# logic_000.net
KiCad netlist of a schematic drawn in Altium Designer
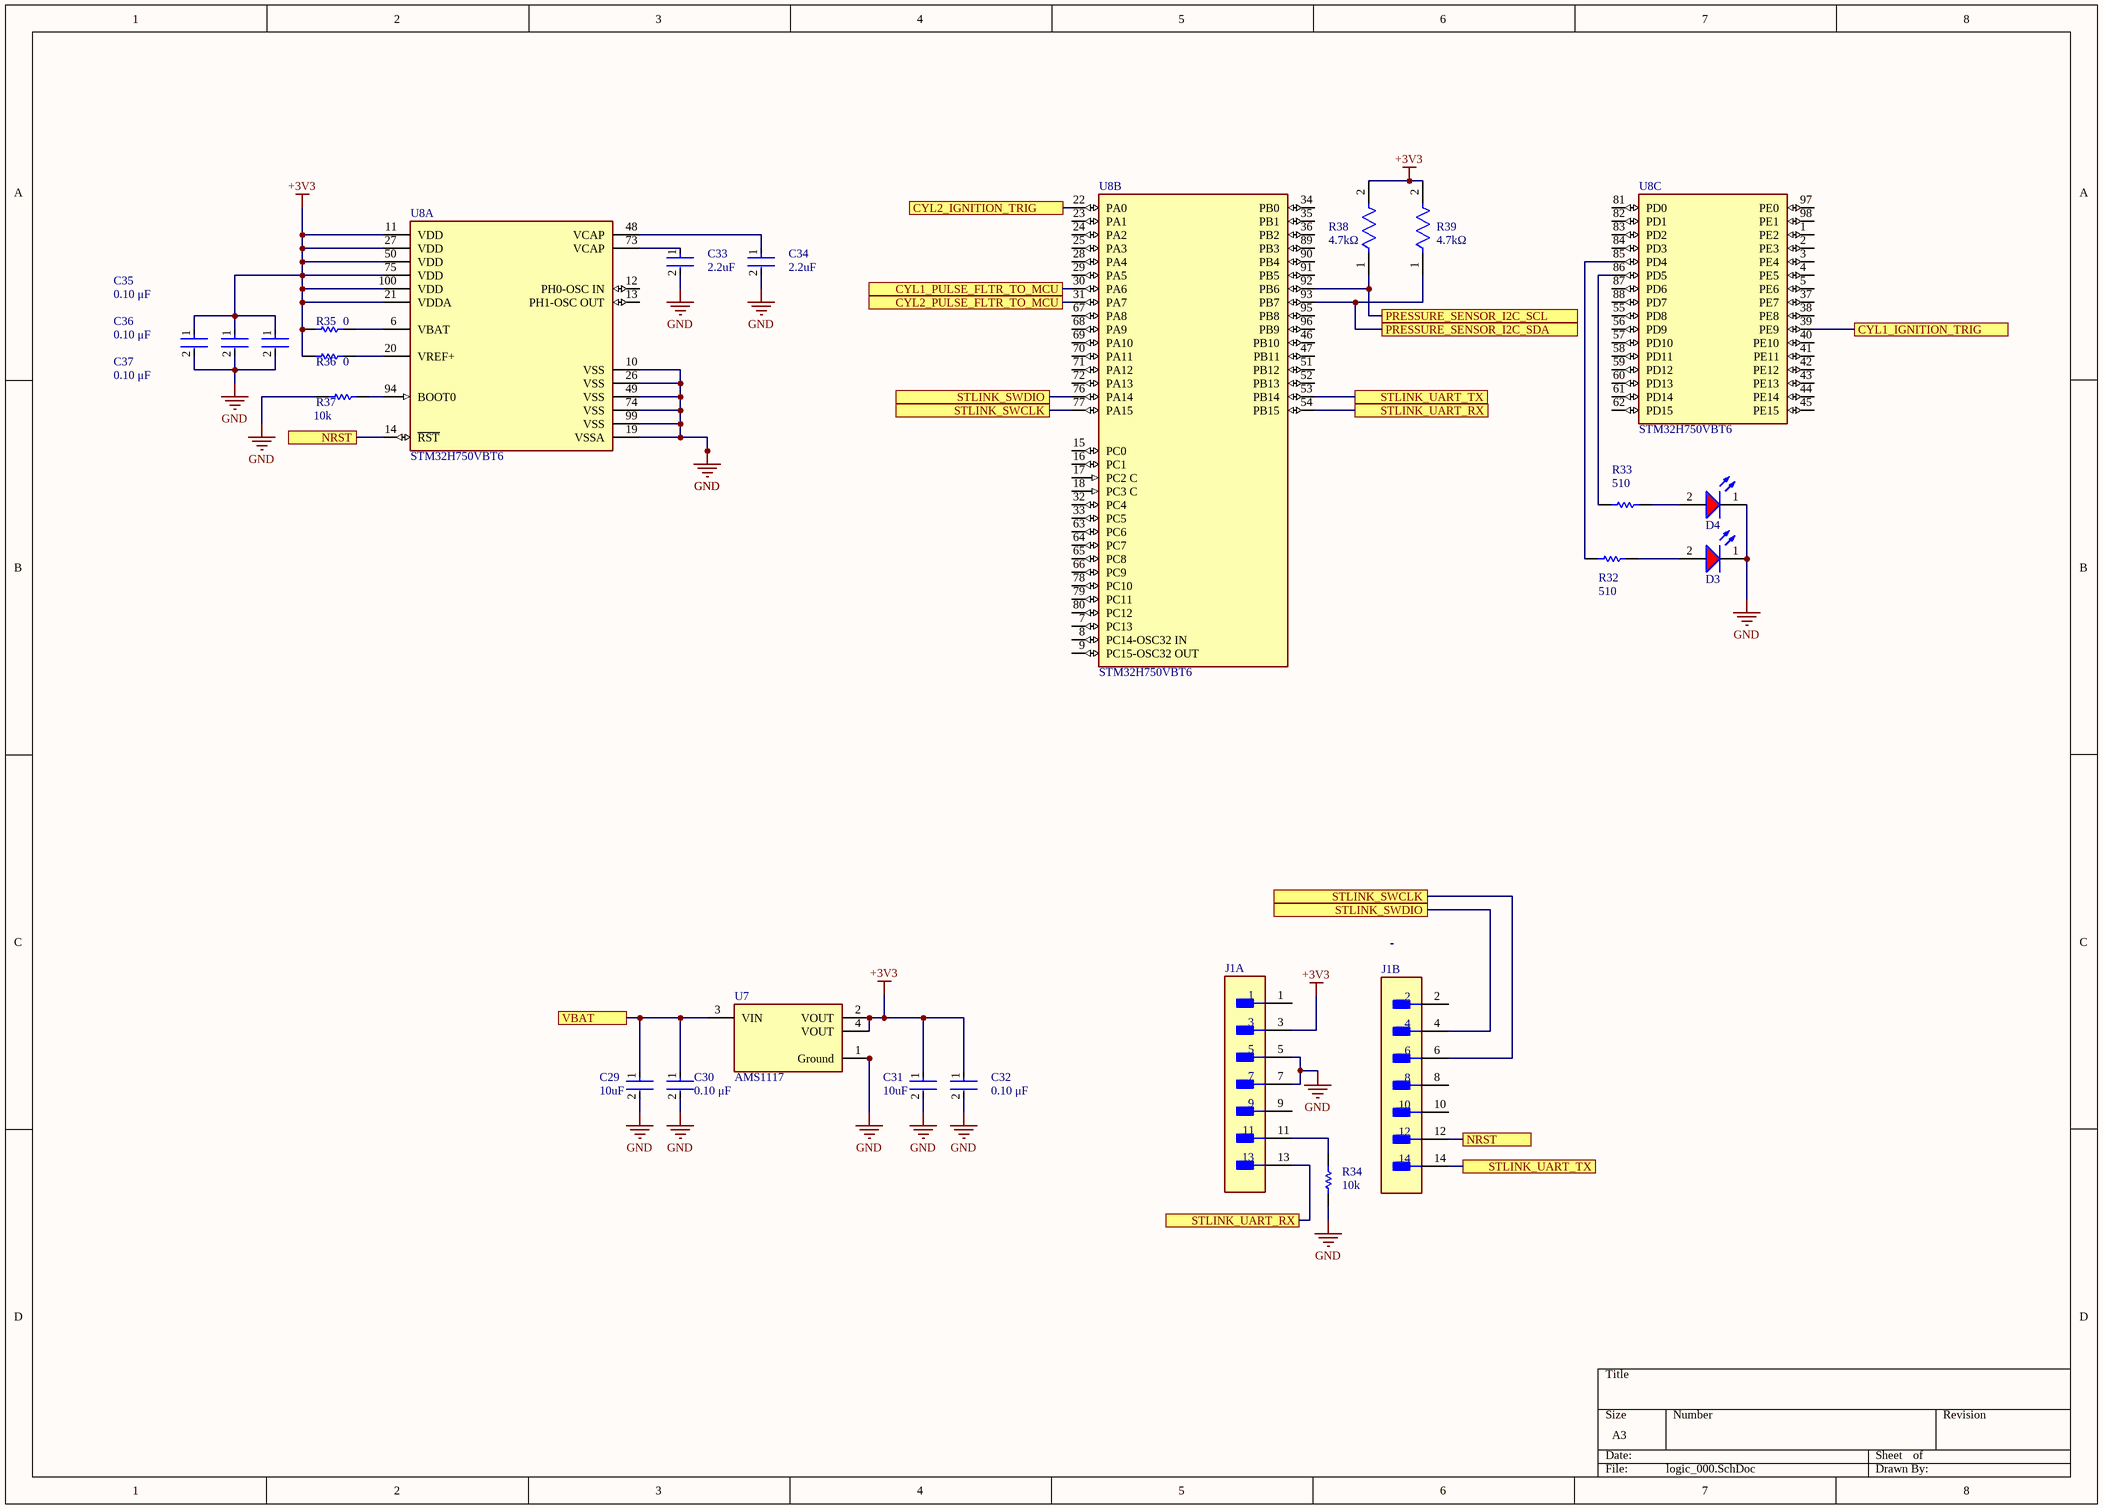
[diagram p0: logic_000.SchDoc]

(export (version "E")
  (design (tool "Eeschema 10.0.6"))
  (components
    (comp (ref "C29")
      (value "CL05A106MP5NUNC")
      (footprint "FP-CL05A106MP5NUNC-MFG")
      (description "CAP CER 10UF 10V X5R 0402")
      (fields
        (field (name "OCTOPART") "https://octopart.com/cl05a106mp5nunc-samsung-22457395")
        (field (name "TOLERANCE") "20%")
        (field (name "CAPACITANCE") "10uF")
      )
      (libsource (lib "Altium Content Vault") (part "b4654b650e69147ec39a6b967a45e02"))
    )
    (comp (ref "C30")
      (value "C0402C104K8PACTU")
      (footprint "FP-C0402-BB-MFG")
      (description "CAP CER 0.1UF 10V X5R 0402")
      (fields
        (field (name "CAPACITANCE") "0.10 μF")
        (field (name "MANUFACTURER") "Kemet")
        (field (name "TOLERANCE") "0.1")
      )
      (libsource (lib "Altium Content Vault") (part "b4654b650e69147ec39a6b967a45e02"))
    )
    (comp (ref "C31")
      (value "CL05A106MP5NUNC")
      (footprint "FP-CL05A106MP5NUNC-MFG")
      (description "CAP CER 10UF 10V X5R 0402")
      (fields
        (field (name "OCTOPART") "https://octopart.com/cl05a106mp5nunc-samsung-22457395")
        (field (name "TOLERANCE") "20%")
        (field (name "CAPACITANCE") "10uF")
      )
      (libsource (lib "Altium Content Vault") (part "b4654b650e69147ec39a6b967a45e02"))
    )
    (comp (ref "C32")
      (value "C0402C104K8PACTU")
      (footprint "FP-C0402-BB-MFG")
      (description "CAP CER 0.1UF 10V X5R 0402")
      (fields
        (field (name "CAPACITANCE") "0.10 μF")
        (field (name "MANUFACTURER") "Kemet")
        (field (name "TOLERANCE") "0.1")
      )
      (libsource (lib "Altium Content Vault") (part "b4654b650e69147ec39a6b967a45e02"))
    )
    (comp (ref "C33")
      (value "GRM155R61A225KE95D")
      (footprint "FP-GRM155-0_05-MFG")
      (description "CAP CER 2.2UF 10V X5R 0402")
      (fields (field (name "CAPACITANCE") "2.2uF") (field (name "TOLERANCE") "10%"))
      (libsource (lib "Altium Content Vault") (part "b4654b650e69147ec39a6b967a45e02"))
    )
    (comp (ref "C34")
      (value "GRM155R61A225KE95D")
      (footprint "FP-GRM155-0_05-MFG")
      (description "CAP CER 2.2UF 10V X5R 0402")
      (fields (field (name "CAPACITANCE") "2.2uF") (field (name "TOLERANCE") "10%"))
      (libsource (lib "Altium Content Vault") (part "b4654b650e69147ec39a6b967a45e02"))
    )
    (comp (ref "C35")
      (value "0.10 μF")
      (footprint "FP-C0402-BB-MFG")
      (description "CAP CER 0.1UF 10V X5R 0402")
      (fields (field (name "MANUFACTURER") "Kemet") (field (name "TOLERANCE") "0.1"))
      (libsource (lib "Altium Content Vault") (part "b4654b650e69147ec39a6b967a45e02"))
    )
    (comp (ref "C36")
      (value "0.10 μF")
      (footprint "FP-C0402-BB-MFG")
      (description "CAP CER 0.1UF 10V X5R 0402")
      (fields (field (name "MANUFACTURER") "Kemet") (field (name "TOLERANCE") "0.1"))
      (libsource (lib "Altium Content Vault") (part "b4654b650e69147ec39a6b967a45e02"))
    )
    (comp (ref "C37")
      (value "0.10 μF")
      (footprint "FP-C0402-BB-MFG")
      (description "CAP CER 0.1UF 10V X5R 0402")
      (fields (field (name "MANUFACTURER") "Kemet") (field (name "TOLERANCE") "0.1"))
      (libsource (lib "Altium Content Vault") (part "b4654b650e69147ec39a6b967a45e02"))
    )
    (comp (ref "D3")
      (value "150080SS75000")
      (footprint "WL-SMCW_0805_150080xx75000")
      (description "Led, Red, 630 Nm, 1.9 V, 30 Ma, 60 Mcd Rohs Compliant: Yes")
      (libsource (lib "Altium Content Vault") (part "LED_Red_2A-1K"))
    )
    (comp (ref "D4")
      (value "150080SS75000")
      (footprint "WL-SMCW_0805_150080xx75000")
      (description "Led, Red, 630 Nm, 1.9 V, 30 Ma, 60 Mcd Rohs Compliant: Yes")
      (libsource (lib "Altium Content Vault") (part "LED_Red_2A-1K"))
    )
    (comp (ref "J1")
      (value "FTSH-107-01-L-DV-K")
      (footprint "FP-FTSH-107-01-L-DV-K-MFG")
      (description "CONN HEADER SMD 14POS 1.27MM")
      (libsource (lib "Altium Content Vault") (part "7644e1a88aa4da17242a9b8d8257442"))
    )
    (comp (ref "R32")
      (value "510")
      (footprint "RESC1005X40X25LL05T10")
      (fields (field (name "MANUFACTURER") "Yageo / Phycomp") (field (name "PART NUMBER") "RC0402FR-07510RL"))
      (libsource (lib "Altium Content Vault") (part "RES"))
    )
    (comp (ref "R33")
      (value "510")
      (footprint "RESC1005X40X25LL05T10")
      (fields (field (name "MANUFACTURER") "Yageo / Phycomp") (field (name "PART NUMBER") "RC0402FR-07510RL"))
      (libsource (lib "Altium Content Vault") (part "RES"))
    )
    (comp (ref "R34")
      (value "10k")
      (footprint "RESC1005X40X25LL05T10")
      (fields (field (name "PART NUMBER") "RC0402FR-0710KL") (field (name "MANUFACTURER") "Yageo / Phycomp"))
      (libsource (lib "Altium Content Vault") (part "RES"))
    )
    (comp (ref "R35")
      (value "0")
      (footprint "RESC1005X40X25NL05T10")
      (fields (field (name "MANUFACTURER") "Yageo / Phycomp") (field (name "PART NUMBER") "RC0402JR-070RL"))
      (libsource (lib "Altium Content Vault") (part "RES"))
    )
    (comp (ref "R36")
      (value "0")
      (footprint "RESC1005X40X25NL05T10")
      (fields (field (name "MANUFACTURER") "Yageo / Phycomp") (field (name "PART NUMBER") "RC0402JR-070RL"))
      (libsource (lib "Altium Content Vault") (part "RES"))
    )
    (comp (ref "R37")
      (value "10k")
      (footprint "RESC1005X40X25LL05T10")
      (fields (field (name "PART NUMBER") "RC0402FR-0710KL") (field (name "MANUFACTURER") "Yageo / Phycomp"))
      (libsource (lib "Altium Content Vault") (part "RES"))
    )
    (comp (ref "R38")
      (value "RC0402JR-074K7L")
      (footprint "FP-RC0402-0_4-MFG")
      (fields (field (name "TOLERANCE") "5%") (field (name "RESISTANCE") "4.7kΩ"))
      (libsource (lib "Altium Content Vault") (part "RC0402JR-074K7L"))
    )
    (comp (ref "R39")
      (value "RC0402JR-074K7L")
      (footprint "FP-RC0402-0_4-MFG")
      (fields (field (name "TOLERANCE") "5%") (field (name "RESISTANCE") "4.7kΩ"))
      (libsource (lib "Altium Content Vault") (part "RC0402JR-074K7L"))
    )
    (comp (ref "U7")
      (value "AMS1117-3.3")
      (footprint "FP-AMS1117-IPC_C")
      (description "LDO Voltage Regulators 1A, 3.3V")
      (fields
        (field (name "PACKAGE") "AMS1117")
        (field (name "OCTOPART") "https://octopart.com/ams1117-3.3-advanced+monolithic+systems-25899300")
        (field (name "MANUFACTURER") "Advanced Monolithic Systems")
      )
      (libsource (lib "Altium Content Vault") (part "8bdbb5f8e77002000e30dd2845d0354"))
    )
    (comp (ref "U8")
      (value "STM32H750VBT6")
      (footprint "FP-LQFP100-1L-MFG")
      (description "IC MCU 32BIT 128KB FLASH 100LQFP")
      (fields
        (field (name "OCTOPART") "https://octopart.com/stm32h750vbt6-stmicroelectronics-94048547")
        (field (name "MANUFACTURER") "STMicroelectronics")
      )
      (libsource (lib "Altium Content Vault") (part "aca449acb2b80670ba40d015d68dc7a"))
    )
  )
  (nets
    (net (code "1") (name "+3V3") (class "Default")
      (node (ref "C31") (pin "1") (pinfunction "1_1") (pintype "passive"))
      (node (ref "C32") (pin "1") (pinfunction "1_1") (pintype "passive"))
      (node (ref "C35") (pin "1") (pinfunction "1_1") (pintype "passive"))
      (node (ref "C36") (pin "1") (pinfunction "1_1") (pintype "passive"))
      (node (ref "C37") (pin "1") (pinfunction "1_1") (pintype "passive"))
      (node (ref "J1") (pin "3") (pinfunction "3_3") (pintype "passive"))
      (node (ref "R35") (pin "1") (pinfunction "1_1") (pintype "passive"))
      (node (ref "R36") (pin "1") (pinfunction "1_1") (pintype "passive"))
      (node (ref "R38") (pin "2") (pinfunction "2_2") (pintype "passive"))
      (node (ref "R39") (pin "2") (pinfunction "2_2") (pintype "passive"))
      (node (ref "U7") (pin "2") (pinfunction "VOUT_2") (pintype "passive"))
      (node (ref "U7") (pin "4") (pinfunction "VOUT_4") (pintype "passive"))
      (node (ref "U8") (pin "100") (pinfunction "VDD_100") (pintype "power_in"))
      (node (ref "U8") (pin "11") (pinfunction "VDD_11") (pintype "power_in"))
      (node (ref "U8") (pin "21") (pinfunction "VDDA_21") (pintype "power_in"))
      (node (ref "U8") (pin "27") (pinfunction "VDD_27") (pintype "power_in"))
      (node (ref "U8") (pin "50") (pinfunction "VDD_50") (pintype "power_in"))
      (node (ref "U8") (pin "75") (pinfunction "VDD_75") (pintype "power_in"))
    )
    (net (code "2") (name "/CYL1_IGNITION_TRIG") (class "Default")
      (node (ref "U8") (pin "39") (pinfunction "PE9_39") (pintype "bidirectional"))
    )
    (net (code "3") (name "/CYL1_PULSE_FLTR_TO_MCU") (class "Default")
      (node (ref "U8") (pin "30") (pinfunction "PA6_30") (pintype "bidirectional"))
    )
    (net (code "4") (name "/CYL2_IGNITION_TRIG") (class "Default")
      (node (ref "U8") (pin "22") (pinfunction "PA0_22") (pintype "bidirectional"))
    )
    (net (code "5") (name "/CYL2_PULSE_FLTR_TO_MCU") (class "Default")
      (node (ref "U8") (pin "31") (pinfunction "PA7_31") (pintype "bidirectional"))
    )
    (net (code "6") (name "/NRST") (class "Default")
      (node (ref "J1") (pin "12") (pinfunction "12_12") (pintype "passive"))
      (node (ref "U8") (pin "14") (pinfunction "~{RST}_14") (pintype "bidirectional"))
    )
    (net (code "7") (name "/PRESSURE_SENSOR_I2C_SCL") (class "Default")
      (node (ref "R38") (pin "1") (pinfunction "1_1") (pintype "passive"))
      (node (ref "U8") (pin "92") (pinfunction "PB6_92") (pintype "bidirectional"))
    )
    (net (code "8") (name "/PRESSURE_SENSOR_I2C_SDA") (class "Default")
      (node (ref "R39") (pin "1") (pinfunction "1_1") (pintype "passive"))
      (node (ref "U8") (pin "93") (pinfunction "PB7_93") (pintype "bidirectional"))
    )
    (net (code "9") (name "/STLINK_SWCLK") (class "Default")
      (node (ref "J1") (pin "6") (pinfunction "6_6") (pintype "passive"))
      (node (ref "U8") (pin "77") (pinfunction "PA15_77") (pintype "bidirectional"))
    )
    (net (code "10") (name "/STLINK_SWDIO") (class "Default")
      (node (ref "J1") (pin "4") (pinfunction "4_4") (pintype "passive"))
      (node (ref "U8") (pin "76") (pinfunction "PA14_76") (pintype "bidirectional"))
    )
    (net (code "11") (name "/STLINK_UART_RX") (class "Default")
      (node (ref "J1") (pin "13") (pinfunction "13_13") (pintype "passive"))
      (node (ref "U8") (pin "54") (pinfunction "PB15_54") (pintype "bidirectional"))
    )
    (net (code "12") (name "/STLINK_UART_TX") (class "Default")
      (node (ref "J1") (pin "14") (pinfunction "14_14") (pintype "passive"))
      (node (ref "U8") (pin "53") (pinfunction "PB14_53") (pintype "bidirectional"))
    )
    (net (code "13") (name "/VBAT") (class "Default")
      (node (ref "C29") (pin "1") (pinfunction "1_1") (pintype "passive"))
      (node (ref "C30") (pin "1") (pinfunction "1_1") (pintype "passive"))
      (node (ref "U7") (pin "3") (pinfunction "VIN_3") (pintype "power_in"))
    )
    (net (code "14") (name "GND") (class "Default")
      (node (ref "C29") (pin "2") (pinfunction "2_2") (pintype "passive"))
      (node (ref "C30") (pin "2") (pinfunction "2_2") (pintype "passive"))
      (node (ref "C31") (pin "2") (pinfunction "2_2") (pintype "passive"))
      (node (ref "C32") (pin "2") (pinfunction "2_2") (pintype "passive"))
      (node (ref "C33") (pin "2") (pinfunction "2_2") (pintype "passive"))
      (node (ref "C34") (pin "2") (pinfunction "2_2") (pintype "passive"))
      (node (ref "C35") (pin "2") (pinfunction "2_2") (pintype "passive"))
      (node (ref "C36") (pin "2") (pinfunction "2_2") (pintype "passive"))
      (node (ref "C37") (pin "2") (pinfunction "2_2") (pintype "passive"))
      (node (ref "D3") (pin "1") (pinfunction "K_1") (pintype "passive"))
      (node (ref "D4") (pin "1") (pinfunction "K_1") (pintype "passive"))
      (node (ref "J1") (pin "5") (pinfunction "5_5") (pintype "passive"))
      (node (ref "J1") (pin "7") (pinfunction "7_7") (pintype "passive"))
      (node (ref "R34") (pin "1") (pinfunction "1_1") (pintype "passive"))
      (node (ref "R37") (pin "1") (pinfunction "1_1") (pintype "passive"))
      (node (ref "U7") (pin "1") (pinfunction "Ground_1") (pintype "power_in"))
      (node (ref "U8") (pin "10") (pinfunction "VSS_10") (pintype "power_in"))
      (node (ref "U8") (pin "19") (pinfunction "VSSA_19") (pintype "power_in"))
      (node (ref "U8") (pin "26") (pinfunction "VSS_26") (pintype "power_in"))
      (node (ref "U8") (pin "49") (pinfunction "VSS_49") (pintype "power_in"))
      (node (ref "U8") (pin "74") (pinfunction "VSS_74") (pintype "power_in"))
      (node (ref "U8") (pin "99") (pinfunction "VSS_99") (pintype "power_in"))
    )
    (net (code "15") (name "Net-(C33-Pad1)") (class "Default")
      (node (ref "C33") (pin "1") (pinfunction "1_1") (pintype "passive"))
      (node (ref "U8") (pin "73") (pinfunction "VCAP_73") (pintype "power_in"))
    )
    (net (code "16") (name "Net-(C34-Pad1)") (class "Default")
      (node (ref "C34") (pin "1") (pinfunction "1_1") (pintype "passive"))
      (node (ref "U8") (pin "48") (pinfunction "VCAP_48") (pintype "power_in"))
    )
    (net (code "17") (name "Net-(D3-A)") (class "Default")
      (node (ref "D3") (pin "2") (pinfunction "A_2") (pintype "passive"))
      (node (ref "R32") (pin "1") (pinfunction "1_1") (pintype "passive"))
    )
    (net (code "18") (name "Net-(D4-A)") (class "Default")
      (node (ref "D4") (pin "2") (pinfunction "A_2") (pintype "passive"))
      (node (ref "R33") (pin "1") (pinfunction "1_1") (pintype "passive"))
    )
    (net (code "19") (name "Net-(J1-Pad11)") (class "Default")
      (node (ref "J1") (pin "11") (pinfunction "11_11") (pintype "passive"))
      (node (ref "R34") (pin "2") (pinfunction "2_2") (pintype "passive"))
    )
    (net (code "20") (name "Net-(U8A-BOOT0)") (class "Default")
      (node (ref "R37") (pin "2") (pinfunction "2_2") (pintype "passive"))
      (node (ref "U8") (pin "94") (pinfunction "BOOT0_94") (pintype "input"))
    )
    (net (code "21") (name "Net-(U8A-VBAT)") (class "Default")
      (node (ref "R35") (pin "2") (pinfunction "2_2") (pintype "passive"))
      (node (ref "U8") (pin "6") (pinfunction "VBAT_6") (pintype "power_in"))
    )
    (net (code "22") (name "Net-(U8A-VREF+)") (class "Default")
      (node (ref "R36") (pin "2") (pinfunction "2_2") (pintype "passive"))
      (node (ref "U8") (pin "20") (pinfunction "VREF+_20") (pintype "power_in"))
    )
    (net (code "23") (name "Net-(U8C-PD4)") (class "Default")
      (node (ref "R32") (pin "2") (pinfunction "2_2") (pintype "passive"))
      (node (ref "U8") (pin "85") (pinfunction "PD4_85") (pintype "bidirectional"))
    )
    (net (code "24") (name "Net-(U8C-PD5)") (class "Default")
      (node (ref "R33") (pin "2") (pinfunction "2_2") (pintype "passive"))
      (node (ref "U8") (pin "86") (pinfunction "PD5_86") (pintype "bidirectional"))
    )
    (net (code "25") (name "unconnected-(J1-Pad1)") (class "Default")
      (node (ref "J1") (pin "1") (pinfunction "1_1") (pintype "passive"))
    )
    (net (code "26") (name "unconnected-(J1-Pad2)") (class "Default")
      (node (ref "J1") (pin "2") (pinfunction "2_2") (pintype "passive"))
    )
    (net (code "27") (name "unconnected-(J1-Pad8)") (class "Default")
      (node (ref "J1") (pin "8") (pinfunction "8_8") (pintype "passive"))
    )
    (net (code "28") (name "unconnected-(J1-Pad9)") (class "Default")
      (node (ref "J1") (pin "9") (pinfunction "9_9") (pintype "passive"))
    )
    (net (code "29") (name "unconnected-(J1-Pad10)") (class "Default")
      (node (ref "J1") (pin "10") (pinfunction "10_10") (pintype "passive"))
    )
    (net (code "30") (name "unconnected-(U8A-PH0-OSC_IN-Pad12)") (class "Default")
      (node (ref "U8") (pin "12") (pinfunction "PH0-OSC_IN_12") (pintype "bidirectional"))
    )
    (net (code "31") (name "unconnected-(U8A-PH1-OSC_OUT-Pad13)") (class "Default")
      (node (ref "U8") (pin "13") (pinfunction "PH1-OSC_OUT_13") (pintype "bidirectional"))
    )
    (net (code "32") (name "unconnected-(U8B-PA1-Pad23)") (class "Default")
      (node (ref "U8") (pin "23") (pinfunction "PA1_23") (pintype "bidirectional"))
    )
    (net (code "33") (name "unconnected-(U8B-PA2-Pad24)") (class "Default")
      (node (ref "U8") (pin "24") (pinfunction "PA2_24") (pintype "bidirectional"))
    )
    (net (code "34") (name "unconnected-(U8B-PA3-Pad25)") (class "Default")
      (node (ref "U8") (pin "25") (pinfunction "PA3_25") (pintype "bidirectional"))
    )
    (net (code "35") (name "unconnected-(U8B-PA4-Pad28)") (class "Default")
      (node (ref "U8") (pin "28") (pinfunction "PA4_28") (pintype "bidirectional"))
    )
    (net (code "36") (name "unconnected-(U8B-PA5-Pad29)") (class "Default")
      (node (ref "U8") (pin "29") (pinfunction "PA5_29") (pintype "bidirectional"))
    )
    (net (code "37") (name "unconnected-(U8B-PA8-Pad67)") (class "Default")
      (node (ref "U8") (pin "67") (pinfunction "PA8_67") (pintype "bidirectional"))
    )
    (net (code "38") (name "unconnected-(U8B-PA9-Pad68)") (class "Default")
      (node (ref "U8") (pin "68") (pinfunction "PA9_68") (pintype "bidirectional"))
    )
    (net (code "39") (name "unconnected-(U8B-PA10-Pad69)") (class "Default")
      (node (ref "U8") (pin "69") (pinfunction "PA10_69") (pintype "bidirectional"))
    )
    (net (code "40") (name "unconnected-(U8B-PA11-Pad70)") (class "Default")
      (node (ref "U8") (pin "70") (pinfunction "PA11_70") (pintype "bidirectional"))
    )
    (net (code "41") (name "unconnected-(U8B-PA12-Pad71)") (class "Default")
      (node (ref "U8") (pin "71") (pinfunction "PA12_71") (pintype "bidirectional"))
    )
    (net (code "42") (name "unconnected-(U8B-PA13-Pad72)") (class "Default")
      (node (ref "U8") (pin "72") (pinfunction "PA13_72") (pintype "bidirectional"))
    )
    (net (code "43") (name "unconnected-(U8B-PB0-Pad34)") (class "Default")
      (node (ref "U8") (pin "34") (pinfunction "PB0_34") (pintype "bidirectional"))
    )
    (net (code "44") (name "unconnected-(U8B-PB1-Pad35)") (class "Default")
      (node (ref "U8") (pin "35") (pinfunction "PB1_35") (pintype "bidirectional"))
    )
    (net (code "45") (name "unconnected-(U8B-PB2-Pad36)") (class "Default")
      (node (ref "U8") (pin "36") (pinfunction "PB2_36") (pintype "bidirectional"))
    )
    (net (code "46") (name "unconnected-(U8B-PB3-Pad89)") (class "Default")
      (node (ref "U8") (pin "89") (pinfunction "PB3_89") (pintype "bidirectional"))
    )
    (net (code "47") (name "unconnected-(U8B-PB4-Pad90)") (class "Default")
      (node (ref "U8") (pin "90") (pinfunction "PB4_90") (pintype "bidirectional"))
    )
    (net (code "48") (name "unconnected-(U8B-PB5-Pad91)") (class "Default")
      (node (ref "U8") (pin "91") (pinfunction "PB5_91") (pintype "bidirectional"))
    )
    (net (code "49") (name "unconnected-(U8B-PB8-Pad95)") (class "Default")
      (node (ref "U8") (pin "95") (pinfunction "PB8_95") (pintype "bidirectional"))
    )
    (net (code "50") (name "unconnected-(U8B-PB9-Pad96)") (class "Default")
      (node (ref "U8") (pin "96") (pinfunction "PB9_96") (pintype "bidirectional"))
    )
    (net (code "51") (name "unconnected-(U8B-PB10-Pad46)") (class "Default")
      (node (ref "U8") (pin "46") (pinfunction "PB10_46") (pintype "bidirectional"))
    )
    (net (code "52") (name "unconnected-(U8B-PB11-Pad47)") (class "Default")
      (node (ref "U8") (pin "47") (pinfunction "PB11_47") (pintype "bidirectional"))
    )
    (net (code "53") (name "unconnected-(U8B-PB12-Pad51)") (class "Default")
      (node (ref "U8") (pin "51") (pinfunction "PB12_51") (pintype "bidirectional"))
    )
    (net (code "54") (name "unconnected-(U8B-PB13-Pad52)") (class "Default")
      (node (ref "U8") (pin "52") (pinfunction "PB13_52") (pintype "bidirectional"))
    )
    (net (code "55") (name "unconnected-(U8B-PC0-Pad15)") (class "Default")
      (node (ref "U8") (pin "15") (pinfunction "PC0_15") (pintype "bidirectional"))
    )
    (net (code "56") (name "unconnected-(U8B-PC1-Pad16)") (class "Default")
      (node (ref "U8") (pin "16") (pinfunction "PC1_16") (pintype "bidirectional"))
    )
    (net (code "57") (name "unconnected-(U8B-PC2_C-Pad17)") (class "Default")
      (node (ref "U8") (pin "17") (pinfunction "PC2_C_17") (pintype "input"))
    )
    (net (code "58") (name "unconnected-(U8B-PC3_C-Pad18)") (class "Default")
      (node (ref "U8") (pin "18") (pinfunction "PC3_C_18") (pintype "input"))
    )
    (net (code "59") (name "unconnected-(U8B-PC4-Pad32)") (class "Default")
      (node (ref "U8") (pin "32") (pinfunction "PC4_32") (pintype "bidirectional"))
    )
    (net (code "60") (name "unconnected-(U8B-PC5-Pad33)") (class "Default")
      (node (ref "U8") (pin "33") (pinfunction "PC5_33") (pintype "bidirectional"))
    )
    (net (code "61") (name "unconnected-(U8B-PC6-Pad63)") (class "Default")
      (node (ref "U8") (pin "63") (pinfunction "PC6_63") (pintype "bidirectional"))
    )
    (net (code "62") (name "unconnected-(U8B-PC7-Pad64)") (class "Default")
      (node (ref "U8") (pin "64") (pinfunction "PC7_64") (pintype "bidirectional"))
    )
    (net (code "63") (name "unconnected-(U8B-PC8-Pad65)") (class "Default")
      (node (ref "U8") (pin "65") (pinfunction "PC8_65") (pintype "bidirectional"))
    )
    (net (code "64") (name "unconnected-(U8B-PC9-Pad66)") (class "Default")
      (node (ref "U8") (pin "66") (pinfunction "PC9_66") (pintype "bidirectional"))
    )
    (net (code "65") (name "unconnected-(U8B-PC10-Pad78)") (class "Default")
      (node (ref "U8") (pin "78") (pinfunction "PC10_78") (pintype "bidirectional"))
    )
    (net (code "66") (name "unconnected-(U8B-PC11-Pad79)") (class "Default")
      (node (ref "U8") (pin "79") (pinfunction "PC11_79") (pintype "bidirectional"))
    )
    (net (code "67") (name "unconnected-(U8B-PC12-Pad80)") (class "Default")
      (node (ref "U8") (pin "80") (pinfunction "PC12_80") (pintype "bidirectional"))
    )
    (net (code "68") (name "unconnected-(U8B-PC13-Pad7)") (class "Default")
      (node (ref "U8") (pin "7") (pinfunction "PC13_7") (pintype "bidirectional"))
    )
    (net (code "69") (name "unconnected-(U8B-PC14-OSC32_IN-Pad8)") (class "Default")
      (node (ref "U8") (pin "8") (pinfunction "PC14-OSC32_IN_8") (pintype "bidirectional"))
    )
    (net (code "70") (name "unconnected-(U8B-PC15-OSC32_OUT-Pad9)") (class "Default")
      (node (ref "U8") (pin "9") (pinfunction "PC15-OSC32_OUT_9") (pintype "bidirectional"))
    )
    (net (code "71") (name "unconnected-(U8C-PD0-Pad81)") (class "Default")
      (node (ref "U8") (pin "81") (pinfunction "PD0_81") (pintype "bidirectional"))
    )
    (net (code "72") (name "unconnected-(U8C-PD1-Pad82)") (class "Default")
      (node (ref "U8") (pin "82") (pinfunction "PD1_82") (pintype "bidirectional"))
    )
    (net (code "73") (name "unconnected-(U8C-PD2-Pad83)") (class "Default")
      (node (ref "U8") (pin "83") (pinfunction "PD2_83") (pintype "bidirectional"))
    )
    (net (code "74") (name "unconnected-(U8C-PD3-Pad84)") (class "Default")
      (node (ref "U8") (pin "84") (pinfunction "PD3_84") (pintype "bidirectional"))
    )
    (net (code "75") (name "unconnected-(U8C-PD6-Pad87)") (class "Default")
      (node (ref "U8") (pin "87") (pinfunction "PD6_87") (pintype "bidirectional"))
    )
    (net (code "76") (name "unconnected-(U8C-PD7-Pad88)") (class "Default")
      (node (ref "U8") (pin "88") (pinfunction "PD7_88") (pintype "bidirectional"))
    )
    (net (code "77") (name "unconnected-(U8C-PD8-Pad55)") (class "Default")
      (node (ref "U8") (pin "55") (pinfunction "PD8_55") (pintype "bidirectional"))
    )
    (net (code "78") (name "unconnected-(U8C-PD9-Pad56)") (class "Default")
      (node (ref "U8") (pin "56") (pinfunction "PD9_56") (pintype "bidirectional"))
    )
    (net (code "79") (name "unconnected-(U8C-PD10-Pad57)") (class "Default")
      (node (ref "U8") (pin "57") (pinfunction "PD10_57") (pintype "bidirectional"))
    )
    (net (code "80") (name "unconnected-(U8C-PD11-Pad58)") (class "Default")
      (node (ref "U8") (pin "58") (pinfunction "PD11_58") (pintype "bidirectional"))
    )
    (net (code "81") (name "unconnected-(U8C-PD12-Pad59)") (class "Default")
      (node (ref "U8") (pin "59") (pinfunction "PD12_59") (pintype "bidirectional"))
    )
    (net (code "82") (name "unconnected-(U8C-PD13-Pad60)") (class "Default")
      (node (ref "U8") (pin "60") (pinfunction "PD13_60") (pintype "bidirectional"))
    )
    (net (code "83") (name "unconnected-(U8C-PD14-Pad61)") (class "Default")
      (node (ref "U8") (pin "61") (pinfunction "PD14_61") (pintype "bidirectional"))
    )
    (net (code "84") (name "unconnected-(U8C-PD15-Pad62)") (class "Default")
      (node (ref "U8") (pin "62") (pinfunction "PD15_62") (pintype "bidirectional"))
    )
    (net (code "85") (name "unconnected-(U8C-PE0-Pad97)") (class "Default")
      (node (ref "U8") (pin "97") (pinfunction "PE0_97") (pintype "bidirectional"))
    )
    (net (code "86") (name "unconnected-(U8C-PE1-Pad98)") (class "Default")
      (node (ref "U8") (pin "98") (pinfunction "PE1_98") (pintype "bidirectional"))
    )
    (net (code "87") (name "unconnected-(U8C-PE2-Pad1)") (class "Default")
      (node (ref "U8") (pin "1") (pinfunction "PE2_1") (pintype "bidirectional"))
    )
    (net (code "88") (name "unconnected-(U8C-PE3-Pad2)") (class "Default")
      (node (ref "U8") (pin "2") (pinfunction "PE3_2") (pintype "bidirectional"))
    )
    (net (code "89") (name "unconnected-(U8C-PE4-Pad3)") (class "Default")
      (node (ref "U8") (pin "3") (pinfunction "PE4_3") (pintype "bidirectional"))
    )
    (net (code "90") (name "unconnected-(U8C-PE5-Pad4)") (class "Default")
      (node (ref "U8") (pin "4") (pinfunction "PE5_4") (pintype "bidirectional"))
    )
    (net (code "91") (name "unconnected-(U8C-PE6-Pad5)") (class "Default")
      (node (ref "U8") (pin "5") (pinfunction "PE6_5") (pintype "bidirectional"))
    )
    (net (code "92") (name "unconnected-(U8C-PE7-Pad37)") (class "Default")
      (node (ref "U8") (pin "37") (pinfunction "PE7_37") (pintype "bidirectional"))
    )
    (net (code "93") (name "unconnected-(U8C-PE8-Pad38)") (class "Default")
      (node (ref "U8") (pin "38") (pinfunction "PE8_38") (pintype "bidirectional"))
    )
    (net (code "94") (name "unconnected-(U8C-PE10-Pad40)") (class "Default")
      (node (ref "U8") (pin "40") (pinfunction "PE10_40") (pintype "bidirectional"))
    )
    (net (code "95") (name "unconnected-(U8C-PE11-Pad41)") (class "Default")
      (node (ref "U8") (pin "41") (pinfunction "PE11_41") (pintype "bidirectional"))
    )
    (net (code "96") (name "unconnected-(U8C-PE12-Pad42)") (class "Default")
      (node (ref "U8") (pin "42") (pinfunction "PE12_42") (pintype "bidirectional"))
    )
    (net (code "97") (name "unconnected-(U8C-PE13-Pad43)") (class "Default")
      (node (ref "U8") (pin "43") (pinfunction "PE13_43") (pintype "bidirectional"))
    )
    (net (code "98") (name "unconnected-(U8C-PE14-Pad44)") (class "Default")
      (node (ref "U8") (pin "44") (pinfunction "PE14_44") (pintype "bidirectional"))
    )
    (net (code "99") (name "unconnected-(U8C-PE15-Pad45)") (class "Default")
      (node (ref "U8") (pin "45") (pinfunction "PE15_45") (pintype "bidirectional"))
    )
  )
)
